# mLRS-tx-module01-v014.net
KiCad netlist of a schematic drawn in EAGLE
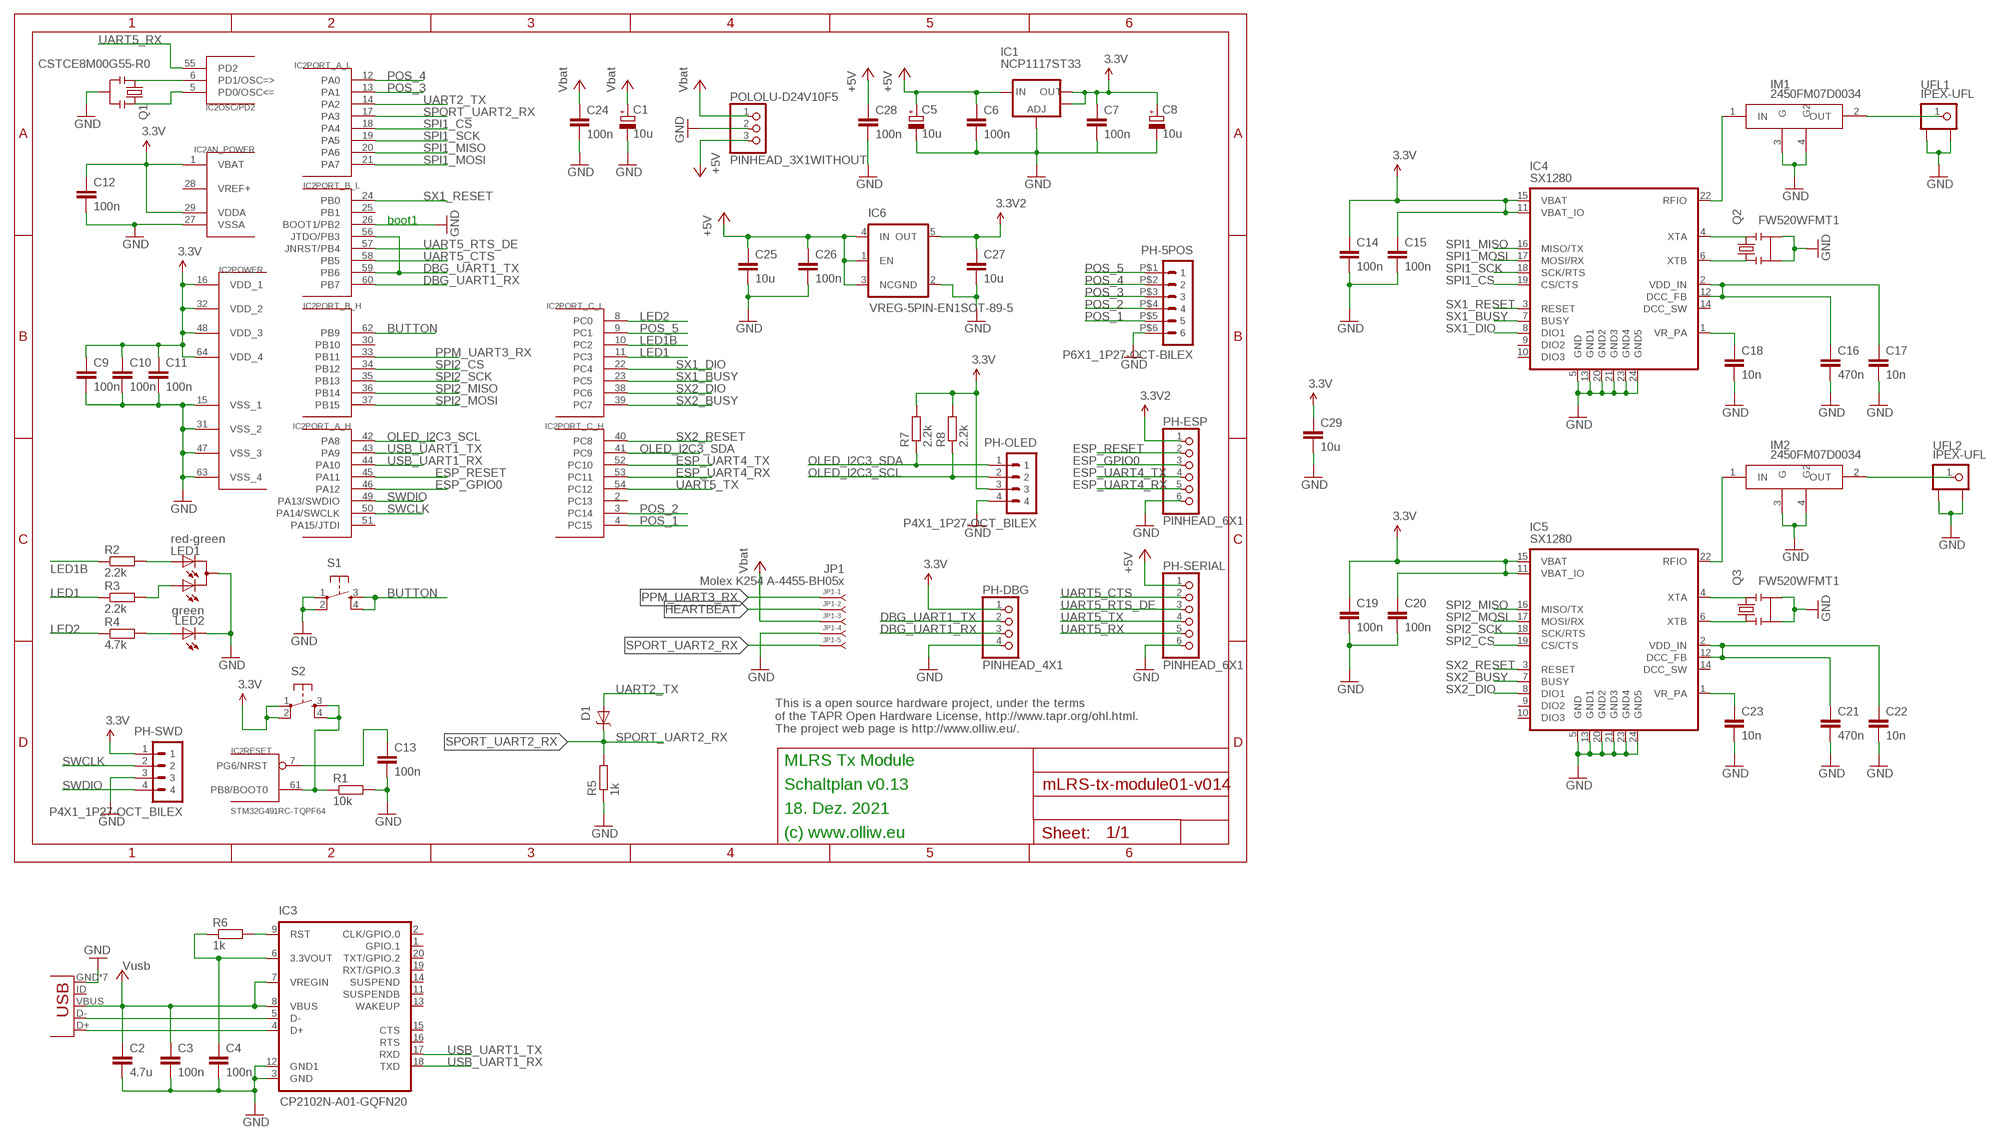
[diagram p0: schematic, sheet 1]

(export (version "E")
  (design (tool "Eeschema 10.0.6"))
  (components
    (comp (ref "C1")
      (value "10u")
      (footprint "eagle-import:SMC_A")
      (libsource (lib "eagle-import") (part "CPOL-EUSMCA"))
    )
    (comp (ref "C2")
      (value "4.7u")
      (footprint "eagle-import:C0603")
      (libsource (lib "eagle-import") (part "C-EUC0603"))
    )
    (comp (ref "C3")
      (value "100n")
      (footprint "eagle-import:C0402")
      (libsource (lib "eagle-import") (part "C-EUC0402"))
    )
    (comp (ref "C4")
      (value "100n")
      (footprint "eagle-import:C0402")
      (libsource (lib "eagle-import") (part "C-EUC0402"))
    )
    (comp (ref "C5")
      (value "10u")
      (footprint "eagle-import:SMC_A")
      (libsource (lib "eagle-import") (part "CPOL-EUSMCA"))
    )
    (comp (ref "C6")
      (value "100n")
      (footprint "eagle-import:C0603")
      (libsource (lib "eagle-import") (part "C-EUC0603"))
    )
    (comp (ref "C7")
      (value "100n")
      (footprint "eagle-import:C0603")
      (libsource (lib "eagle-import") (part "C-EUC0603"))
    )
    (comp (ref "C8")
      (value "10u")
      (footprint "eagle-import:SMC_A")
      (libsource (lib "eagle-import") (part "CPOL-EUSMCA"))
    )
    (comp (ref "C9")
      (value "100n")
      (footprint "eagle-import:C0603")
      (libsource (lib "eagle-import") (part "C-EUC0603"))
    )
    (comp (ref "C10")
      (value "100n")
      (footprint "eagle-import:C0603")
      (libsource (lib "eagle-import") (part "C-EUC0603"))
    )
    (comp (ref "C11")
      (value "100n")
      (footprint "eagle-import:C0603")
      (libsource (lib "eagle-import") (part "C-EUC0603"))
    )
    (comp (ref "C12")
      (value "100n")
      (footprint "eagle-import:C0603")
      (libsource (lib "eagle-import") (part "C-EUC0603"))
    )
    (comp (ref "C13")
      (value "100n")
      (footprint "eagle-import:C0603")
      (libsource (lib "eagle-import") (part "C-EUC0603"))
    )
    (comp (ref "C14")
      (value "100n")
      (footprint "eagle-import:C0402")
      (libsource (lib "eagle-import") (part "C-EUC0402"))
    )
    (comp (ref "C15")
      (value "100n")
      (footprint "eagle-import:C0402")
      (libsource (lib "eagle-import") (part "C-EUC0402"))
    )
    (comp (ref "C16")
      (value "470n")
      (footprint "eagle-import:C0402")
      (libsource (lib "eagle-import") (part "C-EUC0402"))
    )
    (comp (ref "C17")
      (value "10n")
      (footprint "eagle-import:C0402")
      (libsource (lib "eagle-import") (part "C-EUC0402"))
    )
    (comp (ref "C18")
      (value "10n")
      (footprint "eagle-import:C0402")
      (libsource (lib "eagle-import") (part "C-EUC0402"))
    )
    (comp (ref "C19")
      (value "100n")
      (footprint "eagle-import:C0402")
      (libsource (lib "eagle-import") (part "C-EUC0402"))
    )
    (comp (ref "C20")
      (value "100n")
      (footprint "eagle-import:C0402")
      (libsource (lib "eagle-import") (part "C-EUC0402"))
    )
    (comp (ref "C21")
      (value "470n")
      (footprint "eagle-import:C0402")
      (libsource (lib "eagle-import") (part "C-EUC0402"))
    )
    (comp (ref "C22")
      (value "10n")
      (footprint "eagle-import:C0402")
      (libsource (lib "eagle-import") (part "C-EUC0402"))
    )
    (comp (ref "C23")
      (value "10n")
      (footprint "eagle-import:C0402")
      (libsource (lib "eagle-import") (part "C-EUC0402"))
    )
    (comp (ref "C24")
      (value "100n")
      (footprint "eagle-import:C0603")
      (libsource (lib "eagle-import") (part "C-EUC0603"))
    )
    (comp (ref "C25")
      (value "10u")
      (footprint "eagle-import:C0603")
      (libsource (lib "eagle-import") (part "C-EUC0603"))
    )
    (comp (ref "C26")
      (value "100n")
      (footprint "eagle-import:C0603")
      (libsource (lib "eagle-import") (part "C-EUC0603"))
    )
    (comp (ref "C27")
      (value "10u")
      (footprint "eagle-import:C0603")
      (libsource (lib "eagle-import") (part "C-EUC0603"))
    )
    (comp (ref "C28")
      (value "100n")
      (footprint "eagle-import:C0603")
      (libsource (lib "eagle-import") (part "C-EUC0603"))
    )
    (comp (ref "C29")
      (value "10u")
      (footprint "eagle-import:C0603")
      (libsource (lib "eagle-import") (part "C-EUC0603"))
    )
    (comp (ref "D1")
      (value "PMEG3010ER")
      (footprint "eagle-import:SOD123W-DIODE")
      (libsource (lib "eagle-import") (part "DIODE-SCHOTTKYSOD123-W"))
    )
    (comp (ref "IC1")
      (value "NCP1117ST33")
      (footprint "eagle-import:SOT223")
      (libsource (lib "eagle-import") (part "V_REG_LM1117SOT223"))
    )
    (comp (ref "IC2")
      (value "STM32G491RC-TQPF64")
      (footprint "eagle-import:TQFP64")
      (libsource (lib "eagle-import") (part "STM32G4X1RX-TQPF64"))
    )
    (comp (ref "IC3")
      (value "CP2102N-A01-GQFN20")
      (footprint "eagle-import:QFN20-CP2102N")
      (libsource (lib "eagle-import") (part "CP2102N-QFN20"))
    )
    (comp (ref "IC4")
      (value "SX1280")
      (footprint "eagle-import:QFN24-4X4-SX128X")
      (libsource (lib "eagle-import") (part "SX1280"))
    )
    (comp (ref "IC5")
      (value "SX1280")
      (footprint "eagle-import:QFN24-4X4-SX128X")
      (libsource (lib "eagle-import") (part "SX1280"))
    )
    (comp (ref "IC6")
      (value "VREG-5PIN-EN1SOT-89-5")
      (footprint "eagle-import:SOT-89-5")
      (libsource (lib "eagle-import") (part "VREG-5PIN-EN1SOT-89-5"))
    )
    (comp (ref "IM1")
      (value "2450FM07D0034")
      (footprint "eagle-import:SX-IMPEDANCE-MATCH")
      (libsource (lib "eagle-import") (part "SX-IMPEDANCE-MATCH"))
    )
    (comp (ref "IM2")
      (value "2450FM07D0034")
      (footprint "eagle-import:SX-IMPEDANCE-MATCH")
      (libsource (lib "eagle-import") (part "SX-IMPEDANCE-MATCH"))
    )
    (comp (ref "JP1")
      (value "Molex K254 A-4455-BH05x")
      (footprint "eagle-import:4455-B05")
      (libsource (lib "eagle-import") (part "4455-B05_S"))
    )
    (comp (ref "LED1")
      (value "red-green")
      (footprint "eagle-import:LED-DUO-TIGHT")
      (libsource (lib "eagle-import") (part "LED-DUO-C-TIGHT"))
    )
    (comp (ref "LED2")
      (value "green")
      (footprint "eagle-import:LED3MM")
      (libsource (lib "eagle-import") (part "LED3MM"))
    )
    (comp (ref "PH-5POS")
      (value "P6X1_1P27-OCT-BILEX")
      (footprint "eagle-import:6X1_1P27_OCT_BILEX")
      (libsource (lib "eagle-import") (part "P6X1_1P27-OCT-BILEX"))
    )
    (comp (ref "PH-DBG")
      (value "PINHEAD_4X1")
      (footprint "eagle-import:PINHEAD_4X1")
      (libsource (lib "eagle-import") (part "PINHEAD_4X1"))
    )
    (comp (ref "PH-ESP")
      (value "PINHEAD_6X1")
      (footprint "eagle-import:PINHEAD_6X1")
      (libsource (lib "eagle-import") (part "PINHEAD_6X1"))
    )
    (comp (ref "PH-OLED")
      (value "P4X1_1P27-OCT_BILEX")
      (footprint "eagle-import:4X1_1P27_OCT_BILEX")
      (libsource (lib "eagle-import") (part "P4X1_1P27-OCT_BILEX"))
    )
    (comp (ref "PH-SERIAL")
      (value "PINHEAD_6X1")
      (footprint "eagle-import:PINHEAD_6X1")
      (libsource (lib "eagle-import") (part "PINHEAD_6X1"))
    )
    (comp (ref "PH-SWD")
      (value "P4X1_1P27-OCT_BILEX")
      (footprint "eagle-import:4X1_1P27_OCT_BILEX")
      (libsource (lib "eagle-import") (part "P4X1_1P27-OCT_BILEX"))
    )
    (comp (ref "POLOLU-D24V10F5")
      (value "PINHEAD_3X1WITHOUT")
      (footprint "eagle-import:PINHEAD_3X1_WO")
      (libsource (lib "eagle-import") (part "PINHEAD_3X1WITHOUT"))
    )
    (comp (ref "Q1")
      (value "CSTCE8M00G55-R0")
      (footprint "eagle-import:RESONATOR-SMD")
      (libsource (lib "eagle-import") (part "RESONATORSMD"))
    )
    (comp (ref "Q2")
      (value "FW520WFMT1")
      (footprint "eagle-import:CRYSTAL-SMD-2X1P6-GND")
      (libsource (lib "eagle-import") (part "CRYSTAL52MHZ"))
    )
    (comp (ref "Q3")
      (value "FW520WFMT1")
      (footprint "eagle-import:CRYSTAL-SMD-2X1P6-GND")
      (libsource (lib "eagle-import") (part "CRYSTAL52MHZ"))
    )
    (comp (ref "R1")
      (value "10k")
      (footprint "eagle-import:R0402")
      (libsource (lib "eagle-import") (part "R-EU_R0402"))
    )
    (comp (ref "R2")
      (value "2.2k")
      (footprint "eagle-import:R0402")
      (libsource (lib "eagle-import") (part "R-EU_R0402"))
    )
    (comp (ref "R3")
      (value "2.2k")
      (footprint "eagle-import:R0402")
      (libsource (lib "eagle-import") (part "R-EU_R0402"))
    )
    (comp (ref "R4")
      (value "4.7k")
      (footprint "eagle-import:R0402")
      (libsource (lib "eagle-import") (part "R-EU_R0402"))
    )
    (comp (ref "R5")
      (value "1k")
      (footprint "eagle-import:R0402")
      (libsource (lib "eagle-import") (part "R-EU_R0402"))
    )
    (comp (ref "R6")
      (value "1k")
      (footprint "eagle-import:R0402")
      (libsource (lib "eagle-import") (part "R-EU_R0402"))
    )
    (comp (ref "R7")
      (value "2.2k")
      (footprint "eagle-import:R0402")
      (libsource (lib "eagle-import") (part "R-EU_R0402"))
    )
    (comp (ref "R8")
      (value "2.2k")
      (footprint "eagle-import:R0402")
      (libsource (lib "eagle-import") (part "R-EU_R0402"))
    )
    (comp (ref "S1")
      (value "TAC_SWITCHPTH")
      (footprint "eagle-import:TACTILE-PTH")
      (libsource (lib "eagle-import") (part "TAC_SWITCHPTH"))
    )
    (comp (ref "S2")
      (value "TAC_SWITCHPTH")
      (footprint "eagle-import:TACTILE-PTH")
      (libsource (lib "eagle-import") (part "TAC_SWITCHPTH"))
    )
    (comp (ref "UFL1")
      (value "IPEX-UFL")
      (footprint "eagle-import:IPEX-UFL-SMD")
      (libsource (lib "eagle-import") (part "IPEX-UFL"))
    )
    (comp (ref "UFL2")
      (value "IPEX-UFL")
      (footprint "eagle-import:IPEX-UFL-SMD")
      (libsource (lib "eagle-import") (part "IPEX-UFL"))
    )
    (comp (ref "USB")
      (value "USB-MICROB-UP")
      (footprint "eagle-import:USB-MICROB-UP")
      (libsource (lib "eagle-import") (part "USB-MICROB-UP"))
    )
  )
  (nets
    (net (code "1") (name "+5V") (class "Default")
      (node (ref "C25") (pin "1") (pinfunction "1_1") (pintype "passive"))
      (node (ref "C26") (pin "1") (pinfunction "1_1") (pintype "passive"))
      (node (ref "C28") (pin "1") (pinfunction "1_1") (pintype "passive"))
      (node (ref "C5") (pin "+") (pinfunction "+_+") (pintype "passive"))
      (node (ref "C6") (pin "1") (pinfunction "1_1") (pintype "passive"))
      (node (ref "IC1") (pin "3") (pinfunction "IN_3") (pintype "input"))
      (node (ref "IC6") (pin "1") (pinfunction "EN_1") (pintype "input"))
      (node (ref "IC6") (pin "3") (pinfunction "NC_3") (pintype "passive"))
      (node (ref "IC6") (pin "4") (pinfunction "IN_4") (pintype "power_in"))
      (node (ref "PH-SERIAL") (pin "1") (pinfunction "1_1") (pintype "passive"))
      (node (ref "POLOLU-D24V10F5") (pin "3") (pinfunction "5_3") (pintype "passive"))
    )
    (net (code "2") (name "/BUTTON") (class "Default")
      (node (ref "IC2") (pin "62") (pinfunction "PB9_62") (pintype "bidirectional"))
      (node (ref "S1") (pin "3") (pinfunction "3_3") (pintype "passive"))
      (node (ref "S1") (pin "4") (pinfunction "4_4") (pintype "passive"))
    )
    (net (code "3") (name "/DBG_UART1_RX") (class "Default")
      (node (ref "IC2") (pin "60") (pinfunction "PB7_60") (pintype "bidirectional"))
      (node (ref "PH-DBG") (pin "3") (pinfunction "3_3") (pintype "passive"))
    )
    (net (code "4") (name "/DBG_UART1_TX") (class "Default")
      (node (ref "IC2") (pin "56") (pinfunction "JTDO/PB3_56") (pintype "bidirectional"))
      (node (ref "IC2") (pin "59") (pinfunction "PB6_59") (pintype "bidirectional"))
      (node (ref "PH-DBG") (pin "2") (pinfunction "2_2") (pintype "passive"))
    )
    (net (code "5") (name "/ESP_GPIO0") (class "Default")
      (node (ref "IC2") (pin "46") (pinfunction "PA12_46") (pintype "bidirectional"))
      (node (ref "PH-ESP") (pin "3") (pinfunction "3_3") (pintype "passive"))
    )
    (net (code "6") (name "/ESP_RESET") (class "Default")
      (node (ref "IC2") (pin "45") (pinfunction "PA11_45") (pintype "bidirectional"))
      (node (ref "PH-ESP") (pin "2") (pinfunction "2_2") (pintype "passive"))
    )
    (net (code "7") (name "/ESP_UART4_RX") (class "Default")
      (node (ref "IC2") (pin "53") (pinfunction "PC11_53") (pintype "bidirectional"))
      (node (ref "PH-ESP") (pin "5") (pinfunction "5_5") (pintype "passive"))
    )
    (net (code "8") (name "/ESP_UART4_TX") (class "Default")
      (node (ref "IC2") (pin "52") (pinfunction "PC10_52") (pintype "bidirectional"))
      (node (ref "PH-ESP") (pin "4") (pinfunction "4_4") (pintype "passive"))
    )
    (net (code "9") (name "/LED1") (class "Default")
      (node (ref "IC2") (pin "11") (pinfunction "PC3_11") (pintype "bidirectional"))
      (node (ref "R3") (pin "1") (pinfunction "1_1") (pintype "passive"))
    )
    (net (code "10") (name "/LED1B") (class "Default")
      (node (ref "IC2") (pin "10") (pinfunction "PC2_10") (pintype "bidirectional"))
      (node (ref "R2") (pin "1") (pinfunction "1_1") (pintype "passive"))
    )
    (net (code "11") (name "/LED2") (class "Default")
      (node (ref "IC2") (pin "8") (pinfunction "PC0_8") (pintype "bidirectional"))
      (node (ref "R4") (pin "1") (pinfunction "1_1") (pintype "passive"))
    )
    (net (code "12") (name "/OLED_I2C3_SCL") (class "Default")
      (node (ref "IC2") (pin "42") (pinfunction "PA8_42") (pintype "bidirectional"))
      (node (ref "PH-OLED") (pin "2") (pinfunction "2_2") (pintype "passive"))
      (node (ref "R8") (pin "1") (pinfunction "1_1") (pintype "passive"))
    )
    (net (code "13") (name "/OLED_I2C3_SDA") (class "Default")
      (node (ref "IC2") (pin "41") (pinfunction "PC9_41") (pintype "bidirectional"))
      (node (ref "PH-OLED") (pin "1") (pinfunction "1_1") (pintype "passive"))
      (node (ref "R7") (pin "1") (pinfunction "1_1") (pintype "passive"))
    )
    (net (code "14") (name "/POS_1") (class "Default")
      (node (ref "IC2") (pin "4") (pinfunction "PC15_4") (pintype "bidirectional"))
      (node (ref "PH-5POS") (pin "P$5") (pinfunction "5_P$5") (pintype "passive"))
    )
    (net (code "15") (name "/POS_2") (class "Default")
      (node (ref "IC2") (pin "3") (pinfunction "PC14_3") (pintype "bidirectional"))
      (node (ref "PH-5POS") (pin "P$4") (pinfunction "4_P$4") (pintype "passive"))
    )
    (net (code "16") (name "/POS_3") (class "Default")
      (node (ref "IC2") (pin "13") (pinfunction "PA1_13") (pintype "bidirectional"))
      (node (ref "PH-5POS") (pin "P$3") (pinfunction "3_P$3") (pintype "passive"))
    )
    (net (code "17") (name "/POS_4") (class "Default")
      (node (ref "IC2") (pin "12") (pinfunction "PA0_12") (pintype "bidirectional"))
      (node (ref "PH-5POS") (pin "P$2") (pinfunction "2_P$2") (pintype "passive"))
    )
    (net (code "18") (name "/POS_5") (class "Default")
      (node (ref "IC2") (pin "9") (pinfunction "PC1_9") (pintype "bidirectional"))
      (node (ref "PH-5POS") (pin "P$1") (pinfunction "1_P$1") (pintype "passive"))
    )
    (net (code "19") (name "/SPI1_CS") (class "Default")
      (node (ref "IC2") (pin "18") (pinfunction "PA4_18") (pintype "bidirectional"))
      (node (ref "IC4") (pin "19") (pinfunction "CS/CTS_19") (pintype "input"))
    )
    (net (code "20") (name "/SPI1_MISO") (class "Default")
      (node (ref "IC2") (pin "20") (pinfunction "PA6_20") (pintype "bidirectional"))
      (node (ref "IC4") (pin "16") (pinfunction "MISO/TX_16") (pintype "input"))
    )
    (net (code "21") (name "/SPI1_MOSI") (class "Default")
      (node (ref "IC2") (pin "21") (pinfunction "PA7_21") (pintype "bidirectional"))
      (node (ref "IC4") (pin "17") (pinfunction "MOSI/RX_17") (pintype "input"))
    )
    (net (code "22") (name "/SPI1_SCK") (class "Default")
      (node (ref "IC2") (pin "19") (pinfunction "PA5_19") (pintype "bidirectional"))
      (node (ref "IC4") (pin "18") (pinfunction "SCK/RTS_18") (pintype "input"))
    )
    (net (code "23") (name "/SPI2_CS") (class "Default")
      (node (ref "IC2") (pin "34") (pinfunction "PB12_34") (pintype "bidirectional"))
      (node (ref "IC5") (pin "19") (pinfunction "CS/CTS_19") (pintype "input"))
    )
    (net (code "24") (name "/SPI2_MISO") (class "Default")
      (node (ref "IC2") (pin "36") (pinfunction "PB14_36") (pintype "bidirectional"))
      (node (ref "IC5") (pin "16") (pinfunction "MISO/TX_16") (pintype "input"))
    )
    (net (code "25") (name "/SPI2_MOSI") (class "Default")
      (node (ref "IC2") (pin "37") (pinfunction "PB15_37") (pintype "bidirectional"))
      (node (ref "IC5") (pin "17") (pinfunction "MOSI/RX_17") (pintype "input"))
    )
    (net (code "26") (name "/SPI2_SCK") (class "Default")
      (node (ref "IC2") (pin "35") (pinfunction "PB13_35") (pintype "bidirectional"))
      (node (ref "IC5") (pin "18") (pinfunction "SCK/RTS_18") (pintype "input"))
    )
    (net (code "27") (name "/SWCLK") (class "Default")
      (node (ref "IC2") (pin "50") (pinfunction "PA14/SWCLK_50") (pintype "bidirectional"))
      (node (ref "PH-SWD") (pin "2") (pinfunction "2_2") (pintype "passive"))
    )
    (net (code "28") (name "/SWDIO") (class "Default")
      (node (ref "IC2") (pin "49") (pinfunction "PA13/SWDIO_49") (pintype "bidirectional"))
      (node (ref "PH-SWD") (pin "4") (pinfunction "4_4") (pintype "passive"))
    )
    (net (code "29") (name "/SX1_BUSY") (class "Default")
      (node (ref "IC2") (pin "23") (pinfunction "PC5_23") (pintype "bidirectional"))
      (node (ref "IC4") (pin "7") (pinfunction "BUSY_7") (pintype "bidirectional"))
    )
    (net (code "30") (name "/SX1_DIO") (class "Default")
      (node (ref "IC2") (pin "22") (pinfunction "PC4_22") (pintype "bidirectional"))
      (node (ref "IC4") (pin "8") (pinfunction "DIO1_8") (pintype "input"))
    )
    (net (code "31") (name "/SX1_RESET") (class "Default")
      (node (ref "IC2") (pin "24") (pinfunction "PB0_24") (pintype "bidirectional"))
      (node (ref "IC4") (pin "3") (pinfunction "RESET_3") (pintype "bidirectional"))
    )
    (net (code "32") (name "/SX2_BUSY") (class "Default")
      (node (ref "IC2") (pin "39") (pinfunction "PC7_39") (pintype "bidirectional"))
      (node (ref "IC5") (pin "7") (pinfunction "BUSY_7") (pintype "bidirectional"))
    )
    (net (code "33") (name "/SX2_DIO") (class "Default")
      (node (ref "IC2") (pin "38") (pinfunction "PC6_38") (pintype "bidirectional"))
      (node (ref "IC5") (pin "8") (pinfunction "DIO1_8") (pintype "input"))
    )
    (net (code "34") (name "/SX2_RESET") (class "Default")
      (node (ref "IC2") (pin "40") (pinfunction "PC8_40") (pintype "bidirectional"))
      (node (ref "IC5") (pin "3") (pinfunction "RESET_3") (pintype "bidirectional"))
    )
    (net (code "35") (name "/UART2_TX") (class "Default")
      (node (ref "D1") (pin "A") (pinfunction "A_A") (pintype "passive"))
      (node (ref "IC2") (pin "14") (pinfunction "PA2_14") (pintype "bidirectional"))
    )
    (net (code "36") (name "/UART5_CTS") (class "Default")
      (node (ref "IC2") (pin "58") (pinfunction "PB5_58") (pintype "bidirectional"))
      (node (ref "PH-SERIAL") (pin "2") (pinfunction "2_2") (pintype "passive"))
    )
    (net (code "37") (name "/UART5_RTS_DE") (class "Default")
      (node (ref "IC2") (pin "57") (pinfunction "JNRST/PB4_57") (pintype "bidirectional"))
      (node (ref "PH-SERIAL") (pin "3") (pinfunction "3_3") (pintype "passive"))
    )
    (net (code "38") (name "/UART5_RX") (class "Default")
      (node (ref "IC2") (pin "55") (pinfunction "PD2_55") (pintype "bidirectional"))
      (node (ref "PH-SERIAL") (pin "5") (pinfunction "5_5") (pintype "passive"))
    )
    (net (code "39") (name "/UART5_TX") (class "Default")
      (node (ref "IC2") (pin "54") (pinfunction "PC12_54") (pintype "bidirectional"))
      (node (ref "PH-SERIAL") (pin "4") (pinfunction "4_4") (pintype "passive"))
    )
    (net (code "40") (name "/USB_UART1_RX") (class "Default")
      (node (ref "IC2") (pin "44") (pinfunction "PA10_44") (pintype "bidirectional"))
      (node (ref "IC3") (pin "18") (pinfunction "TXD_18") (pintype "output"))
    )
    (net (code "41") (name "/USB_UART1_TX") (class "Default")
      (node (ref "IC2") (pin "43") (pinfunction "PA9_43") (pintype "bidirectional"))
      (node (ref "IC3") (pin "17") (pinfunction "RXD_17") (pintype "input"))
    )
    (net (code "42") (name "3.3V") (class "Default")
      (node (ref "C10") (pin "1") (pinfunction "1_1") (pintype "passive"))
      (node (ref "C11") (pin "1") (pinfunction "1_1") (pintype "passive"))
      (node (ref "C12") (pin "1") (pinfunction "1_1") (pintype "passive"))
      (node (ref "C14") (pin "1") (pinfunction "1_1") (pintype "passive"))
      (node (ref "C15") (pin "1") (pinfunction "1_1") (pintype "passive"))
      (node (ref "C19") (pin "1") (pinfunction "1_1") (pintype "passive"))
      (node (ref "C20") (pin "1") (pinfunction "1_1") (pintype "passive"))
      (node (ref "C29") (pin "1") (pinfunction "1_1") (pintype "passive"))
      (node (ref "C7") (pin "1") (pinfunction "1_1") (pintype "passive"))
      (node (ref "C8") (pin "+") (pinfunction "+_+") (pintype "passive"))
      (node (ref "C9") (pin "1") (pinfunction "1_1") (pintype "passive"))
      (node (ref "IC1") (pin "2") (pinfunction "OUT_2") (pintype "output"))
      (node (ref "IC1") (pin "4") (pinfunction "OUT_4") (pintype "output"))
      (node (ref "IC2") (pin "1") (pinfunction "VBAT_1") (pintype "power_in"))
      (node (ref "IC2") (pin "16") (pinfunction "VDD_1_16") (pintype "power_in"))
      (node (ref "IC2") (pin "29") (pinfunction "VDDA_29") (pintype "power_in"))
      (node (ref "IC2") (pin "32") (pinfunction "VDD_2_32") (pintype "power_in"))
      (node (ref "IC2") (pin "48") (pinfunction "VDD_3_48") (pintype "power_in"))
      (node (ref "IC2") (pin "64") (pinfunction "VDD_4_64") (pintype "power_in"))
      (node (ref "IC4") (pin "11") (pinfunction "VBAT_IO_11") (pintype "power_in"))
      (node (ref "IC4") (pin "15") (pinfunction "VBAT_15") (pintype "power_in"))
      (node (ref "IC5") (pin "11") (pinfunction "VBAT_IO_11") (pintype "power_in"))
      (node (ref "IC5") (pin "15") (pinfunction "VBAT_15") (pintype "power_in"))
      (node (ref "PH-DBG") (pin "1") (pinfunction "1_1") (pintype "passive"))
      (node (ref "PH-OLED") (pin "3") (pinfunction "3_3") (pintype "passive"))
      (node (ref "PH-SWD") (pin "1") (pinfunction "1_1") (pintype "passive"))
      (node (ref "R7") (pin "2") (pinfunction "2_2") (pintype "passive"))
      (node (ref "R8") (pin "2") (pinfunction "2_2") (pintype "passive"))
      (node (ref "S2") (pin "1") (pinfunction "1_1") (pintype "passive"))
      (node (ref "S2") (pin "2") (pinfunction "2_2") (pintype "passive"))
    )
    (net (code "43") (name "3.3V2") (class "Default")
      (node (ref "C27") (pin "1") (pinfunction "1_1") (pintype "passive"))
      (node (ref "IC6") (pin "5") (pinfunction "OUT_5") (pintype "output"))
      (node (ref "PH-ESP") (pin "1") (pinfunction "1_1") (pintype "passive"))
    )
    (net (code "44") (name "GND") (class "Default")
      (node (ref "C1") (pin "-") (pinfunction "-_-") (pintype "passive"))
      (node (ref "C10") (pin "2") (pinfunction "2_2") (pintype "passive"))
      (node (ref "C11") (pin "2") (pinfunction "2_2") (pintype "passive"))
      (node (ref "C12") (pin "2") (pinfunction "2_2") (pintype "passive"))
      (node (ref "C13") (pin "2") (pinfunction "2_2") (pintype "passive"))
      (node (ref "C14") (pin "2") (pinfunction "2_2") (pintype "passive"))
      (node (ref "C15") (pin "2") (pinfunction "2_2") (pintype "passive"))
      (node (ref "C16") (pin "2") (pinfunction "2_2") (pintype "passive"))
      (node (ref "C17") (pin "2") (pinfunction "2_2") (pintype "passive"))
      (node (ref "C18") (pin "2") (pinfunction "2_2") (pintype "passive"))
      (node (ref "C19") (pin "2") (pinfunction "2_2") (pintype "passive"))
      (node (ref "C2") (pin "2") (pinfunction "2_2") (pintype "passive"))
      (node (ref "C20") (pin "2") (pinfunction "2_2") (pintype "passive"))
      (node (ref "C21") (pin "2") (pinfunction "2_2") (pintype "passive"))
      (node (ref "C22") (pin "2") (pinfunction "2_2") (pintype "passive"))
      (node (ref "C23") (pin "2") (pinfunction "2_2") (pintype "passive"))
      (node (ref "C24") (pin "2") (pinfunction "2_2") (pintype "passive"))
      (node (ref "C25") (pin "2") (pinfunction "2_2") (pintype "passive"))
      (node (ref "C26") (pin "2") (pinfunction "2_2") (pintype "passive"))
      (node (ref "C27") (pin "2") (pinfunction "2_2") (pintype "passive"))
      (node (ref "C28") (pin "2") (pinfunction "2_2") (pintype "passive"))
      (node (ref "C29") (pin "2") (pinfunction "2_2") (pintype "passive"))
      (node (ref "C3") (pin "2") (pinfunction "2_2") (pintype "passive"))
      (node (ref "C4") (pin "2") (pinfunction "2_2") (pintype "passive"))
      (node (ref "C5") (pin "-") (pinfunction "-_-") (pintype "passive"))
      (node (ref "C6") (pin "2") (pinfunction "2_2") (pintype "passive"))
      (node (ref "C7") (pin "2") (pinfunction "2_2") (pintype "passive"))
      (node (ref "C8") (pin "-") (pinfunction "-_-") (pintype "passive"))
      (node (ref "C9") (pin "2") (pinfunction "2_2") (pintype "passive"))
      (node (ref "IC1") (pin "1") (pinfunction "ADJ_1") (pintype "input"))
      (node (ref "IC2") (pin "15") (pinfunction "VSS_1_15") (pintype "power_in"))
      (node (ref "IC2") (pin "26") (pinfunction "BOOT1/PB2_26") (pintype "bidirectional"))
      (node (ref "IC2") (pin "27") (pinfunction "VSSA_27") (pintype "power_in"))
      (node (ref "IC2") (pin "31") (pinfunction "VSS_2_31") (pintype "power_in"))
      (node (ref "IC2") (pin "47") (pinfunction "VSS_3_47") (pintype "power_in"))
      (node (ref "IC2") (pin "63") (pinfunction "VSS_4_63") (pintype "power_in"))
      (node (ref "IC3") (pin "12") (pinfunction "GND1_12") (pintype "power_in"))
      (node (ref "IC3") (pin "3") (pinfunction "GND_3") (pintype "power_in"))
      (node (ref "IC4") (pin "13") (pinfunction "GND1_13") (pintype "power_in"))
      (node (ref "IC4") (pin "20") (pinfunction "GND2_20") (pintype "power_in"))
      (node (ref "IC4") (pin "21") (pinfunction "GND3_21") (pintype "power_in"))
      (node (ref "IC4") (pin "23") (pinfunction "GND4_23") (pintype "power_in"))
      (node (ref "IC4") (pin "24") (pinfunction "GND5_24") (pintype "power_in"))
      (node (ref "IC4") (pin "5") (pinfunction "GND_5") (pintype "power_in"))
      (node (ref "IC5") (pin "13") (pinfunction "GND1_13") (pintype "power_in"))
      (node (ref "IC5") (pin "20") (pinfunction "GND2_20") (pintype "power_in"))
      (node (ref "IC5") (pin "21") (pinfunction "GND3_21") (pintype "power_in"))
      (node (ref "IC5") (pin "23") (pinfunction "GND4_23") (pintype "power_in"))
      (node (ref "IC5") (pin "24") (pinfunction "GND5_24") (pintype "power_in"))
      (node (ref "IC5") (pin "5") (pinfunction "GND_5") (pintype "power_in"))
      (node (ref "IC6") (pin "2") (pinfunction "GND_2") (pintype "power_in"))
      (node (ref "IM1") (pin "3") (pinfunction "G_3") (pintype "power_in"))
      (node (ref "IM1") (pin "4") (pinfunction "G2_4") (pintype "power_in"))
      (node (ref "IM2") (pin "3") (pinfunction "G_3") (pintype "power_in"))
      (node (ref "IM2") (pin "4") (pinfunction "G2_4") (pintype "power_in"))
      (node (ref "JP1") (pin "4") (pinfunction "J_4") (pintype "passive"))
      (node (ref "LED1") (pin "K") (pinfunction "C_K") (pintype "passive"))
      (node (ref "LED2") (pin "K") (pinfunction "C_K") (pintype "passive"))
      (node (ref "PH-5POS") (pin "P$6") (pinfunction "6_P$6") (pintype "passive"))
      (node (ref "PH-DBG") (pin "4") (pinfunction "4_4") (pintype "passive"))
      (node (ref "PH-ESP") (pin "6") (pinfunction "6_6") (pintype "passive"))
      (node (ref "PH-OLED") (pin "4") (pinfunction "4_4") (pintype "passive"))
      (node (ref "PH-SERIAL") (pin "6") (pinfunction "6_6") (pintype "passive"))
      (node (ref "PH-SWD") (pin "3") (pinfunction "3_3") (pintype "passive"))
      (node (ref "POLOLU-D24V10F5") (pin "2") (pinfunction "3_2") (pintype "passive"))
      (node (ref "Q1") (pin "2") (pinfunction "2_2") (pintype "passive"))
      (node (ref "Q2") (pin "2") (pinfunction "2_2") (pintype "passive"))
      (node (ref "Q2") (pin "4") (pinfunction "4_4") (pintype "passive"))
      (node (ref "Q3") (pin "2") (pinfunction "2_2") (pintype "passive"))
      (node (ref "Q3") (pin "4") (pinfunction "4_4") (pintype "passive"))
      (node (ref "R1") (pin "2") (pinfunction "2_2") (pintype "passive"))
      (node (ref "R5") (pin "1") (pinfunction "1_1") (pintype "passive"))
      (node (ref "S1") (pin "1") (pinfunction "1_1") (pintype "passive"))
      (node (ref "S1") (pin "2") (pinfunction "2_2") (pintype "passive"))
      (node (ref "UFL1") (pin "2") (pinfunction "2_2") (pintype "power_in"))
      (node (ref "UFL1") (pin "3") (pinfunction "3_3") (pintype "power_in"))
      (node (ref "UFL2") (pin "2") (pinfunction "2_2") (pintype "power_in"))
      (node (ref "UFL2") (pin "3") (pinfunction "3_3") (pintype "power_in"))
      (node (ref "USB") (pin "GND") (pinfunction "GND_GND") (pintype "bidirectional"))
      (node (ref "USB") (pin "P$1") (pinfunction "GND_P$1") (pintype "bidirectional"))
      (node (ref "USB") (pin "P$2") (pinfunction "GND_P$2") (pintype "bidirectional"))
      (node (ref "USB") (pin "P$3") (pinfunction "GND_P$3") (pintype "bidirectional"))
      (node (ref "USB") (pin "P$4") (pinfunction "GND_P$4") (pintype "bidirectional"))
      (node (ref "USB") (pin "P$5") (pinfunction "GND_P$5") (pintype "bidirectional"))
      (node (ref "USB") (pin "P$6") (pinfunction "GND_P$6") (pintype "bidirectional"))
    )
    (net (code "45") (name "HEARTBEAT") (class "Default")
      (node (ref "JP1") (pin "2") (pinfunction "J_2") (pintype "passive"))
    )
    (net (code "46") (name "Net-(IC2B-PD0{slash}OSC<=)") (class "Default")
      (node (ref "IC2") (pin "5") (pinfunction "PD0/OSC<=_5") (pintype "bidirectional"))
      (node (ref "Q1") (pin "3") (pinfunction "3_3") (pintype "passive"))
    )
    (net (code "47") (name "Net-(IC2B-PD1{slash}OSC=>)") (class "Default")
      (node (ref "IC2") (pin "6") (pinfunction "PD1/OSC=>_6") (pintype "bidirectional"))
      (node (ref "Q1") (pin "1") (pinfunction "1_1") (pintype "passive"))
    )
    (net (code "48") (name "Net-(IC2J-PB8{slash}BOOT0)") (class "Default")
      (node (ref "IC2") (pin "61") (pinfunction "PB8/BOOT0_61") (pintype "input"))
      (node (ref "R1") (pin "1") (pinfunction "1_1") (pintype "passive"))
      (node (ref "S2") (pin "3") (pinfunction "3_3") (pintype "passive"))
      (node (ref "S2") (pin "4") (pinfunction "4_4") (pintype "passive"))
    )
    (net (code "49") (name "Net-(IC2J-PG6{slash}NRST)") (class "Default")
      (node (ref "C13") (pin "1") (pinfunction "1_1") (pintype "passive"))
      (node (ref "IC2") (pin "7") (pinfunction "PG6/NRST_7") (pintype "input"))
    )
    (net (code "50") (name "Net-(IC3-3.3VOUT)") (class "Default")
      (node (ref "C4") (pin "1") (pinfunction "1_1") (pintype "passive"))
      (node (ref "IC3") (pin "6") (pinfunction "3.3VOUT_6") (pintype "power_in"))
      (node (ref "R6") (pin "1") (pinfunction "1_1") (pintype "passive"))
    )
    (net (code "51") (name "Net-(IC3-D+)") (class "Default")
      (node (ref "IC3") (pin "4") (pinfunction "D+_4") (pintype "bidirectional"))
      (node (ref "USB") (pin "D+") (pinfunction "D+_D+") (pintype "bidirectional"))
    )
    (net (code "52") (name "Net-(IC3-D-)") (class "Default")
      (node (ref "IC3") (pin "5") (pinfunction "D-_5") (pintype "bidirectional"))
      (node (ref "USB") (pin "D-") (pinfunction "D-_D-") (pintype "bidirectional"))
    )
    (net (code "53") (name "Net-(IC3-RST)") (class "Default")
      (node (ref "IC3") (pin "9") (pinfunction "RST_9") (pintype "input"))
      (node (ref "R6") (pin "2") (pinfunction "2_2") (pintype "passive"))
    )
    (net (code "54") (name "Net-(IC4-DCC_FB)") (class "Default")
      (node (ref "C16") (pin "1") (pinfunction "1_1") (pintype "passive"))
      (node (ref "C17") (pin "1") (pinfunction "1_1") (pintype "passive"))
      (node (ref "IC4") (pin "12") (pinfunction "DCC_FB_12") (pintype "bidirectional"))
      (node (ref "IC4") (pin "2") (pinfunction "VDD_IN_2") (pintype "power_in"))
    )
    (net (code "55") (name "Net-(IC4-RFIO)") (class "Default")
      (node (ref "IC4") (pin "22") (pinfunction "RFIO_22") (pintype "bidirectional"))
      (node (ref "IM1") (pin "1") (pinfunction "IN_1") (pintype "bidirectional"))
    )
    (net (code "56") (name "Net-(IC4-VR_PA)") (class "Default")
      (node (ref "C18") (pin "1") (pinfunction "1_1") (pintype "passive"))
      (node (ref "IC4") (pin "1") (pinfunction "VR_PA_1") (pintype "bidirectional"))
    )
    (net (code "57") (name "Net-(IC4-XTA)") (class "Default")
      (node (ref "IC4") (pin "4") (pinfunction "XTA_4") (pintype "bidirectional"))
      (node (ref "Q2") (pin "3") (pinfunction "3_3") (pintype "passive"))
    )
    (net (code "58") (name "Net-(IC4-XTB)") (class "Default")
      (node (ref "IC4") (pin "6") (pinfunction "XTB_6") (pintype "bidirectional"))
      (node (ref "Q2") (pin "1") (pinfunction "1_1") (pintype "passive"))
    )
    (net (code "59") (name "Net-(IC5-DCC_FB)") (class "Default")
      (node (ref "C21") (pin "1") (pinfunction "1_1") (pintype "passive"))
      (node (ref "C22") (pin "1") (pinfunction "1_1") (pintype "passive"))
      (node (ref "IC5") (pin "12") (pinfunction "DCC_FB_12") (pintype "bidirectional"))
      (node (ref "IC5") (pin "2") (pinfunction "VDD_IN_2") (pintype "power_in"))
    )
    (net (code "60") (name "Net-(IC5-RFIO)") (class "Default")
      (node (ref "IC5") (pin "22") (pinfunction "RFIO_22") (pintype "bidirectional"))
      (node (ref "IM2") (pin "1") (pinfunction "IN_1") (pintype "bidirectional"))
    )
    (net (code "61") (name "Net-(IC5-VR_PA)") (class "Default")
      (node (ref "C23") (pin "1") (pinfunction "1_1") (pintype "passive"))
      (node (ref "IC5") (pin "1") (pinfunction "VR_PA_1") (pintype "bidirectional"))
    )
    (net (code "62") (name "Net-(IC5-XTA)") (class "Default")
      (node (ref "IC5") (pin "4") (pinfunction "XTA_4") (pintype "bidirectional"))
      (node (ref "Q3") (pin "3") (pinfunction "3_3") (pintype "passive"))
    )
    (net (code "63") (name "Net-(IC5-XTB)") (class "Default")
      (node (ref "IC5") (pin "6") (pinfunction "XTB_6") (pintype "bidirectional"))
      (node (ref "Q3") (pin "1") (pinfunction "1_1") (pintype "passive"))
    )
    (net (code "64") (name "Net-(IM1-OUT)") (class "Default")
      (node (ref "IM1") (pin "2") (pinfunction "OUT_2") (pintype "bidirectional"))
      (node (ref "UFL1") (pin "1") (pinfunction "1_1") (pintype "passive"))
    )
    (net (code "65") (name "Net-(IM2-OUT)") (class "Default")
      (node (ref "IM2") (pin "2") (pinfunction "OUT_2") (pintype "bidirectional"))
      (node (ref "UFL2") (pin "1") (pinfunction "1_1") (pintype "passive"))
    )
    (net (code "66") (name "Net-(LED1-PadA1)") (class "Default")
      (node (ref "LED1") (pin "A1") (pinfunction "A1_A1") (pintype "passive"))
      (node (ref "R3") (pin "2") (pinfunction "2_2") (pintype "passive"))
    )
    (net (code "67") (name "Net-(LED1-PadA2)") (class "Default")
      (node (ref "LED1") (pin "A2") (pinfunction "A2_A2") (pintype "passive"))
      (node (ref "R2") (pin "2") (pinfunction "2_2") (pintype "passive"))
    )
    (net (code "68") (name "Net-(LED2-PadA)") (class "Default")
      (node (ref "LED2") (pin "A") (pinfunction "A_A") (pintype "passive"))
      (node (ref "R4") (pin "2") (pinfunction "2_2") (pintype "passive"))
    )
    (net (code "69") (name "PPM_UART3_RX") (class "Default")
      (node (ref "IC2") (pin "33") (pinfunction "PB11_33") (pintype "bidirectional"))
      (node (ref "JP1") (pin "1") (pinfunction "J_1") (pintype "passive"))
    )
    (net (code "70") (name "SPORT_UART2_RX") (class "Default")
      (node (ref "D1") (pin "C") (pinfunction "C_C") (pintype "passive"))
      (node (ref "IC2") (pin "17") (pinfunction "PA3_17") (pintype "bidirectional"))
      (node (ref "JP1") (pin "5") (pinfunction "J_5") (pintype "passive"))
      (node (ref "R5") (pin "2") (pinfunction "2_2") (pintype "passive"))
    )
    (net (code "71") (name "Vbat") (class "Default")
      (node (ref "C1") (pin "+") (pinfunction "+_+") (pintype "passive"))
      (node (ref "C24") (pin "1") (pinfunction "1_1") (pintype "passive"))
      (node (ref "JP1") (pin "3") (pinfunction "J_3") (pintype "passive"))
      (node (ref "POLOLU-D24V10F5") (pin "1") (pinfunction "1_1") (pintype "passive"))
    )
    (net (code "72") (name "Vusb") (class "Default")
      (node (ref "C2") (pin "1") (pinfunction "1_1") (pintype "passive"))
      (node (ref "C3") (pin "1") (pinfunction "1_1") (pintype "passive"))
      (node (ref "IC3") (pin "7") (pinfunction "VREGIN_7") (pintype "power_in"))
      (node (ref "IC3") (pin "8") (pinfunction "VBUS_8") (pintype "input"))
      (node (ref "USB") (pin "VBUS") (pinfunction "VBUS_VBUS") (pintype "bidirectional"))
    )
    (net (code "73") (name "unconnected-(IC2A-VREF+-Pad28)") (class "Default")
      (node (ref "IC2") (pin "28") (pinfunction "VREF+_28") (pintype "input"))
    )
    (net (code "74") (name "unconnected-(IC2C-PA15{slash}JTDI-Pad51)") (class "Default")
      (node (ref "IC2") (pin "51") (pinfunction "PA15/JTDI_51") (pintype "bidirectional"))
    )
    (net (code "75") (name "unconnected-(IC2E-PB10-Pad30)") (class "Default")
      (node (ref "IC2") (pin "30") (pinfunction "PB10_30") (pintype "bidirectional"))
    )
    (net (code "76") (name "unconnected-(IC2F-PB1-Pad25)") (class "Default")
      (node (ref "IC2") (pin "25") (pinfunction "PB1_25") (pintype "bidirectional"))
    )
    (net (code "77") (name "unconnected-(IC2G-PC13-Pad2)") (class "Default")
      (node (ref "IC2") (pin "2") (pinfunction "PC13_2") (pintype "bidirectional"))
    )
    (net (code "78") (name "unconnected-(IC3-CLK{slash}GPIO.0-Pad2)") (class "Default")
      (node (ref "IC3") (pin "2") (pinfunction "CLK/GPIO.0_2") (pintype "bidirectional"))
    )
    (net (code "79") (name "unconnected-(IC3-CTS-Pad15)") (class "Default")
      (node (ref "IC3") (pin "15") (pinfunction "CTS_15") (pintype "input"))
    )
    (net (code "80") (name "unconnected-(IC3-GPIO.1-Pad1)") (class "Default")
      (node (ref "IC3") (pin "1") (pinfunction "GPIO.1_1") (pintype "bidirectional"))
    )
    (net (code "81") (name "unconnected-(IC3-RTS-Pad16)") (class "Default")
      (node (ref "IC3") (pin "16") (pinfunction "RTS_16") (pintype "output"))
    )
    (net (code "82") (name "unconnected-(IC3-RXT{slash}GPIO.3-Pad19)") (class "Default")
      (node (ref "IC3") (pin "19") (pinfunction "RXT/GPIO.3_19") (pintype "bidirectional"))
    )
    (net (code "83") (name "unconnected-(IC3-SUSPEND-Pad14)") (class "Default")
      (node (ref "IC3") (pin "14") (pinfunction "SUSPEND_14") (pintype "output"))
    )
    (net (code "84") (name "unconnected-(IC3-SUSPENDB-Pad11)") (class "Default")
      (node (ref "IC3") (pin "11") (pinfunction "SUSPENDB_11") (pintype "output"))
    )
    (net (code "85") (name "unconnected-(IC3-TXT{slash}GPIO.2-Pad20)") (class "Default")
      (node (ref "IC3") (pin "20") (pinfunction "TXT/GPIO.2_20") (pintype "bidirectional"))
    )
    (net (code "86") (name "unconnected-(IC3-WAKEUP-Pad13)") (class "Default")
      (node (ref "IC3") (pin "13") (pinfunction "WAKEUP_13") (pintype "input"))
    )
    (net (code "87") (name "unconnected-(IC4-DCC_SW-Pad14)") (class "Default")
      (node (ref "IC4") (pin "14") (pinfunction "DCC_SW_14") (pintype "bidirectional"))
    )
    (net (code "88") (name "unconnected-(IC4-DIO2-Pad9)") (class "Default")
      (node (ref "IC4") (pin "9") (pinfunction "DIO2_9") (pintype "input"))
    )
    (net (code "89") (name "unconnected-(IC4-DIO3-Pad10)") (class "Default")
      (node (ref "IC4") (pin "10") (pinfunction "DIO3_10") (pintype "input"))
    )
    (net (code "90") (name "unconnected-(IC5-DCC_SW-Pad14)") (class "Default")
      (node (ref "IC5") (pin "14") (pinfunction "DCC_SW_14") (pintype "bidirectional"))
    )
    (net (code "91") (name "unconnected-(IC5-DIO2-Pad9)") (class "Default")
      (node (ref "IC5") (pin "9") (pinfunction "DIO2_9") (pintype "input"))
    )
    (net (code "92") (name "unconnected-(IC5-DIO3-Pad10)") (class "Default")
      (node (ref "IC5") (pin "10") (pinfunction "DIO3_10") (pintype "input"))
    )
    (net (code "93") (name "unconnected-(USB-PadID)") (class "Default")
      (node (ref "USB") (pin "ID") (pinfunction "ID_ID") (pintype "bidirectional"))
    )
  )
)
